# NODEMCU_ESP8266.net
KiCad netlist of a schematic drawn in EAGLE
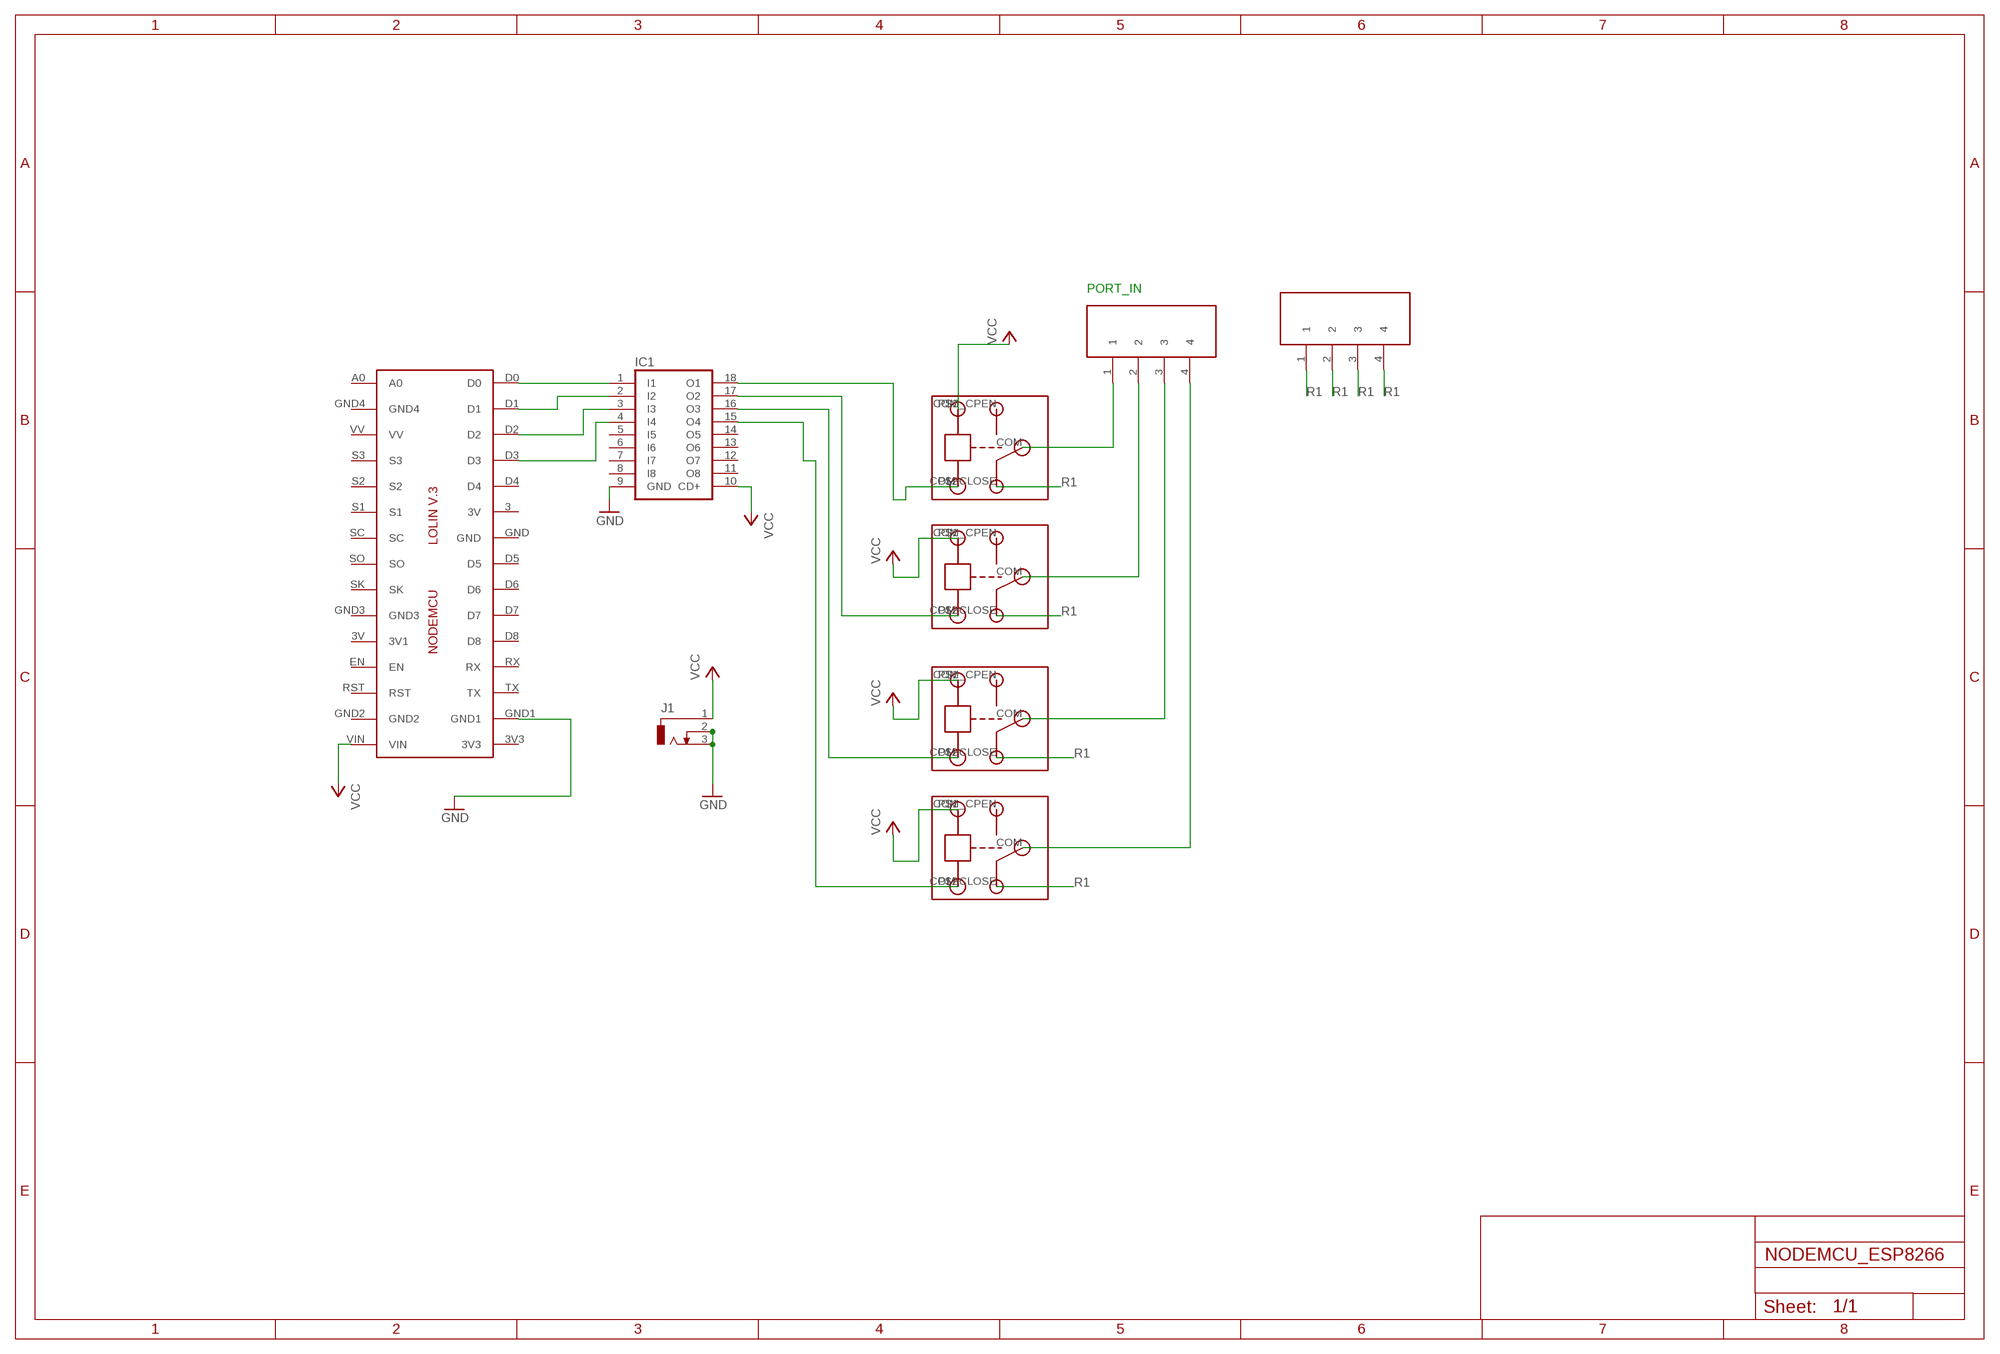
[diagram p0: schematic, sheet 1]

(export (version "E")
  (design (tool "Eeschema 10.0.6"))
  (components
    (comp (ref "IC1")
      (value "ULN2803A")
      (footprint "eagle-import:DIL18")
      (libsource (lib "eagle-import") (part "ULN2803A"))
    )
    (comp (ref "IC2")
      (value "LOLINV3")
      (footprint "eagle-import:LOLINV3")
      (libsource (lib "eagle-import") (part "LOLINV3"))
    )
    (comp (ref "J1")
      (value "DCJ0303")
      (footprint "eagle-import:DCJ0303")
      (libsource (lib "eagle-import") (part "DCJ0303"))
    )
    (comp (ref "PORT_GND")
      (value "LIB_TERMINAL_4_PORT_9.5MM")
      (footprint "eagle-import:LIB_TERMINAL_4_PORT_9.5MM")
      (libsource (lib "eagle-import") (part "LIB_TERMINAL_4_PORT_9.5MM"))
    )
    (comp (ref "U$2")
      (value "RELAY")
      (footprint "eagle-import:RELAY")
      (libsource (lib "eagle-import") (part "RELAY"))
    )
    (comp (ref "U$3")
      (value "RELAY")
      (footprint "eagle-import:RELAY")
      (libsource (lib "eagle-import") (part "RELAY"))
    )
    (comp (ref "U$4")
      (value "RELAY")
      (footprint "eagle-import:RELAY")
      (libsource (lib "eagle-import") (part "RELAY"))
    )
    (comp (ref "U$5")
      (value "RELAY")
      (footprint "eagle-import:RELAY")
      (libsource (lib "eagle-import") (part "RELAY"))
    )
    (comp (ref "U$6")
      (value "LIB_TERMINAL_4_PORT_9.5MM")
      (footprint "eagle-import:LIB_TERMINAL_4_PORT_9.5MM")
      (libsource (lib "eagle-import") (part "LIB_TERMINAL_4_PORT_9.5MM"))
    )
  )
  (nets
    (net (code "1") (name "/R1") (class "Default")
      (node (ref "PORT_GND") (pin "1") (pinfunction "1_1") (pintype "bidirectional"))
      (node (ref "PORT_GND") (pin "2") (pinfunction "2_2") (pintype "bidirectional"))
      (node (ref "PORT_GND") (pin "3") (pinfunction "3_3") (pintype "bidirectional"))
      (node (ref "PORT_GND") (pin "4") (pinfunction "4_4") (pintype "bidirectional"))
      (node (ref "U$2") (pin "COM-CLOSE") (pinfunction "COM-CLOSE_COM-CLOSE") (pintype "bidirectional"))
      (node (ref "U$3") (pin "COM-CLOSE") (pinfunction "COM-CLOSE_COM-CLOSE") (pintype "bidirectional"))
      (node (ref "U$4") (pin "COM-CLOSE") (pinfunction "COM-CLOSE_COM-CLOSE") (pintype "bidirectional"))
      (node (ref "U$5") (pin "COM-CLOSE") (pinfunction "COM-CLOSE_COM-CLOSE") (pintype "bidirectional"))
    )
    (net (code "2") (name "GND") (class "Default")
      (node (ref "IC1") (pin "9") (pinfunction "GND_9") (pintype "power_in"))
      (node (ref "IC2") (pin "GND1") (pinfunction "GND1_GND1") (pintype "bidirectional"))
      (node (ref "J1") (pin "2") (pinfunction "2_2") (pintype "passive"))
      (node (ref "J1") (pin "3") (pinfunction "3_3") (pintype "passive"))
    )
    (net (code "3") (name "Net-(IC1-I1)") (class "Default")
      (node (ref "IC1") (pin "1") (pinfunction "I1_1") (pintype "input"))
      (node (ref "IC2") (pin "D0") (pinfunction "D0_D0") (pintype "bidirectional"))
    )
    (net (code "4") (name "Net-(IC1-I2)") (class "Default")
      (node (ref "IC1") (pin "2") (pinfunction "I2_2") (pintype "input"))
      (node (ref "IC2") (pin "D1") (pinfunction "D1_D1") (pintype "bidirectional"))
    )
    (net (code "5") (name "Net-(IC1-I3)") (class "Default")
      (node (ref "IC1") (pin "3") (pinfunction "I3_3") (pintype "input"))
      (node (ref "IC2") (pin "D2") (pinfunction "D2_D2") (pintype "bidirectional"))
    )
    (net (code "6") (name "Net-(IC1-I4)") (class "Default")
      (node (ref "IC1") (pin "4") (pinfunction "I4_4") (pintype "input"))
      (node (ref "IC2") (pin "D3") (pinfunction "D3_D3") (pintype "bidirectional"))
    )
    (net (code "7") (name "Net-(IC1-O1)") (class "Default")
      (node (ref "IC1") (pin "18") (pinfunction "O1_18") (pintype "open_collector"))
      (node (ref "U$5") (pin "P$2") (pinfunction "GND_P$2") (pintype "bidirectional"))
    )
    (net (code "8") (name "Net-(IC1-O2)") (class "Default")
      (node (ref "IC1") (pin "17") (pinfunction "O2_17") (pintype "open_collector"))
      (node (ref "U$3") (pin "P$2") (pinfunction "GND_P$2") (pintype "bidirectional"))
    )
    (net (code "9") (name "Net-(IC1-O3)") (class "Default")
      (node (ref "IC1") (pin "16") (pinfunction "O3_16") (pintype "open_collector"))
      (node (ref "U$2") (pin "P$2") (pinfunction "GND_P$2") (pintype "bidirectional"))
    )
    (net (code "10") (name "Net-(IC1-O4)") (class "Default")
      (node (ref "IC1") (pin "15") (pinfunction "O4_15") (pintype "open_collector"))
      (node (ref "U$4") (pin "P$2") (pinfunction "GND_P$2") (pintype "bidirectional"))
    )
    (net (code "11") (name "Net-(U$2-PadCOM)") (class "Default")
      (node (ref "U$2") (pin "COM") (pinfunction "COM_COM") (pintype "bidirectional"))
      (node (ref "U$6") (pin "3") (pinfunction "3_3") (pintype "bidirectional"))
    )
    (net (code "12") (name "Net-(U$3-PadCOM)") (class "Default")
      (node (ref "U$3") (pin "COM") (pinfunction "COM_COM") (pintype "bidirectional"))
      (node (ref "U$6") (pin "2") (pinfunction "2_2") (pintype "bidirectional"))
    )
    (net (code "13") (name "Net-(U$4-PadCOM)") (class "Default")
      (node (ref "U$4") (pin "COM") (pinfunction "COM_COM") (pintype "bidirectional"))
      (node (ref "U$6") (pin "4") (pinfunction "4_4") (pintype "bidirectional"))
    )
    (net (code "14") (name "Net-(U$5-PadCOM)") (class "Default")
      (node (ref "U$5") (pin "COM") (pinfunction "COM_COM") (pintype "bidirectional"))
      (node (ref "U$6") (pin "1") (pinfunction "1_1") (pintype "bidirectional"))
    )
    (net (code "15") (name "VCC") (class "Default")
      (node (ref "IC1") (pin "10") (pinfunction "CD+_10") (pintype "passive"))
      (node (ref "IC2") (pin "VIN") (pinfunction "VIN_VIN") (pintype "bidirectional"))
      (node (ref "J1") (pin "1") (pinfunction "1_1") (pintype "passive"))
      (node (ref "U$2") (pin "P$1") (pinfunction "IN_P$1") (pintype "bidirectional"))
      (node (ref "U$3") (pin "P$1") (pinfunction "IN_P$1") (pintype "bidirectional"))
      (node (ref "U$4") (pin "P$1") (pinfunction "IN_P$1") (pintype "bidirectional"))
      (node (ref "U$5") (pin "P$1") (pinfunction "IN_P$1") (pintype "bidirectional"))
    )
    (net (code "16") (name "unconnected-(IC1-I5-Pad5)") (class "Default")
      (node (ref "IC1") (pin "5") (pinfunction "I5_5") (pintype "input"))
    )
    (net (code "17") (name "unconnected-(IC1-I6-Pad6)") (class "Default")
      (node (ref "IC1") (pin "6") (pinfunction "I6_6") (pintype "input"))
    )
    (net (code "18") (name "unconnected-(IC1-I7-Pad7)") (class "Default")
      (node (ref "IC1") (pin "7") (pinfunction "I7_7") (pintype "input"))
    )
    (net (code "19") (name "unconnected-(IC1-I8-Pad8)") (class "Default")
      (node (ref "IC1") (pin "8") (pinfunction "I8_8") (pintype "input"))
    )
    (net (code "20") (name "unconnected-(IC1-O5-Pad14)") (class "Default")
      (node (ref "IC1") (pin "14") (pinfunction "O5_14") (pintype "open_collector"))
    )
    (net (code "21") (name "unconnected-(IC1-O6-Pad13)") (class "Default")
      (node (ref "IC1") (pin "13") (pinfunction "O6_13") (pintype "open_collector"))
    )
    (net (code "22") (name "unconnected-(IC1-O7-Pad12)") (class "Default")
      (node (ref "IC1") (pin "12") (pinfunction "O7_12") (pintype "open_collector"))
    )
    (net (code "23") (name "unconnected-(IC1-O8-Pad11)") (class "Default")
      (node (ref "IC1") (pin "11") (pinfunction "O8_11") (pintype "open_collector"))
    )
    (net (code "24") (name "unconnected-(IC2-3V-Pad3)") (class "Default")
      (node (ref "IC2") (pin "3") (pinfunction "3V_3") (pintype "bidirectional"))
    )
    (net (code "25") (name "unconnected-(IC2-3V1-Pad3V)") (class "Default")
      (node (ref "IC2") (pin "3V") (pinfunction "3V1_3V") (pintype "bidirectional"))
    )
    (net (code "26") (name "unconnected-(IC2-Pad3V3)") (class "Default")
      (node (ref "IC2") (pin "3V3") (pinfunction "3V3_3V3") (pintype "bidirectional"))
    )
    (net (code "27") (name "unconnected-(IC2-PadA0)") (class "Default")
      (node (ref "IC2") (pin "A0") (pinfunction "A0_A0") (pintype "bidirectional"))
    )
    (net (code "28") (name "unconnected-(IC2-PadD4)") (class "Default")
      (node (ref "IC2") (pin "D4") (pinfunction "D4_D4") (pintype "bidirectional"))
    )
    (net (code "29") (name "unconnected-(IC2-PadD5)") (class "Default")
      (node (ref "IC2") (pin "D5") (pinfunction "D5_D5") (pintype "bidirectional"))
    )
    (net (code "30") (name "unconnected-(IC2-PadD6)") (class "Default")
      (node (ref "IC2") (pin "D6") (pinfunction "D6_D6") (pintype "bidirectional"))
    )
    (net (code "31") (name "unconnected-(IC2-PadD7)") (class "Default")
      (node (ref "IC2") (pin "D7") (pinfunction "D7_D7") (pintype "bidirectional"))
    )
    (net (code "32") (name "unconnected-(IC2-PadD8)") (class "Default")
      (node (ref "IC2") (pin "D8") (pinfunction "D8_D8") (pintype "bidirectional"))
    )
    (net (code "33") (name "unconnected-(IC2-PadEN)") (class "Default")
      (node (ref "IC2") (pin "EN") (pinfunction "EN_EN") (pintype "bidirectional"))
    )
    (net (code "34") (name "unconnected-(IC2-PadGND)") (class "Default")
      (node (ref "IC2") (pin "GND") (pinfunction "GND_GND") (pintype "bidirectional"))
    )
    (net (code "35") (name "unconnected-(IC2-PadGND2)") (class "Default")
      (node (ref "IC2") (pin "GND2") (pinfunction "GND2_GND2") (pintype "bidirectional"))
    )
    (net (code "36") (name "unconnected-(IC2-PadGND3)") (class "Default")
      (node (ref "IC2") (pin "GND3") (pinfunction "GND3_GND3") (pintype "bidirectional"))
    )
    (net (code "37") (name "unconnected-(IC2-PadGND4)") (class "Default")
      (node (ref "IC2") (pin "GND4") (pinfunction "GND4_GND4") (pintype "bidirectional"))
    )
    (net (code "38") (name "unconnected-(IC2-PadRST)") (class "Default")
      (node (ref "IC2") (pin "RST") (pinfunction "RST_RST") (pintype "bidirectional"))
    )
    (net (code "39") (name "unconnected-(IC2-PadRX)") (class "Default")
      (node (ref "IC2") (pin "RX") (pinfunction "RX_RX") (pintype "bidirectional"))
    )
    (net (code "40") (name "unconnected-(IC2-PadS1)") (class "Default")
      (node (ref "IC2") (pin "S1") (pinfunction "S1_S1") (pintype "bidirectional"))
    )
    (net (code "41") (name "unconnected-(IC2-PadS2)") (class "Default")
      (node (ref "IC2") (pin "S2") (pinfunction "S2_S2") (pintype "bidirectional"))
    )
    (net (code "42") (name "unconnected-(IC2-PadS3)") (class "Default")
      (node (ref "IC2") (pin "S3") (pinfunction "S3_S3") (pintype "bidirectional"))
    )
    (net (code "43") (name "unconnected-(IC2-PadSC)") (class "Default")
      (node (ref "IC2") (pin "SC") (pinfunction "SC_SC") (pintype "bidirectional"))
    )
    (net (code "44") (name "unconnected-(IC2-PadSK)") (class "Default")
      (node (ref "IC2") (pin "SK") (pinfunction "SK_SK") (pintype "bidirectional"))
    )
    (net (code "45") (name "unconnected-(IC2-PadSO)") (class "Default")
      (node (ref "IC2") (pin "SO") (pinfunction "SO_SO") (pintype "bidirectional"))
    )
    (net (code "46") (name "unconnected-(IC2-PadTX)") (class "Default")
      (node (ref "IC2") (pin "TX") (pinfunction "TX_TX") (pintype "bidirectional"))
    )
    (net (code "47") (name "unconnected-(IC2-PadVV)") (class "Default")
      (node (ref "IC2") (pin "VV") (pinfunction "VV_VV") (pintype "bidirectional"))
    )
    (net (code "48") (name "unconnected-(U$2-COM-OPEN-PadCOM_CPEN)") (class "Default")
      (node (ref "U$2") (pin "COM_CPEN") (pinfunction "COM-OPEN_COM_CPEN") (pintype "bidirectional"))
    )
    (net (code "49") (name "unconnected-(U$3-COM-OPEN-PadCOM_CPEN)") (class "Default")
      (node (ref "U$3") (pin "COM_CPEN") (pinfunction "COM-OPEN_COM_CPEN") (pintype "bidirectional"))
    )
    (net (code "50") (name "unconnected-(U$4-COM-OPEN-PadCOM_CPEN)") (class "Default")
      (node (ref "U$4") (pin "COM_CPEN") (pinfunction "COM-OPEN_COM_CPEN") (pintype "bidirectional"))
    )
    (net (code "51") (name "unconnected-(U$5-COM-OPEN-PadCOM_CPEN)") (class "Default")
      (node (ref "U$5") (pin "COM_CPEN") (pinfunction "COM-OPEN_COM_CPEN") (pintype "bidirectional"))
    )
  )
)
